# SmartSoilSensor.net
KiCad netlist of a schematic drawn in EAGLE
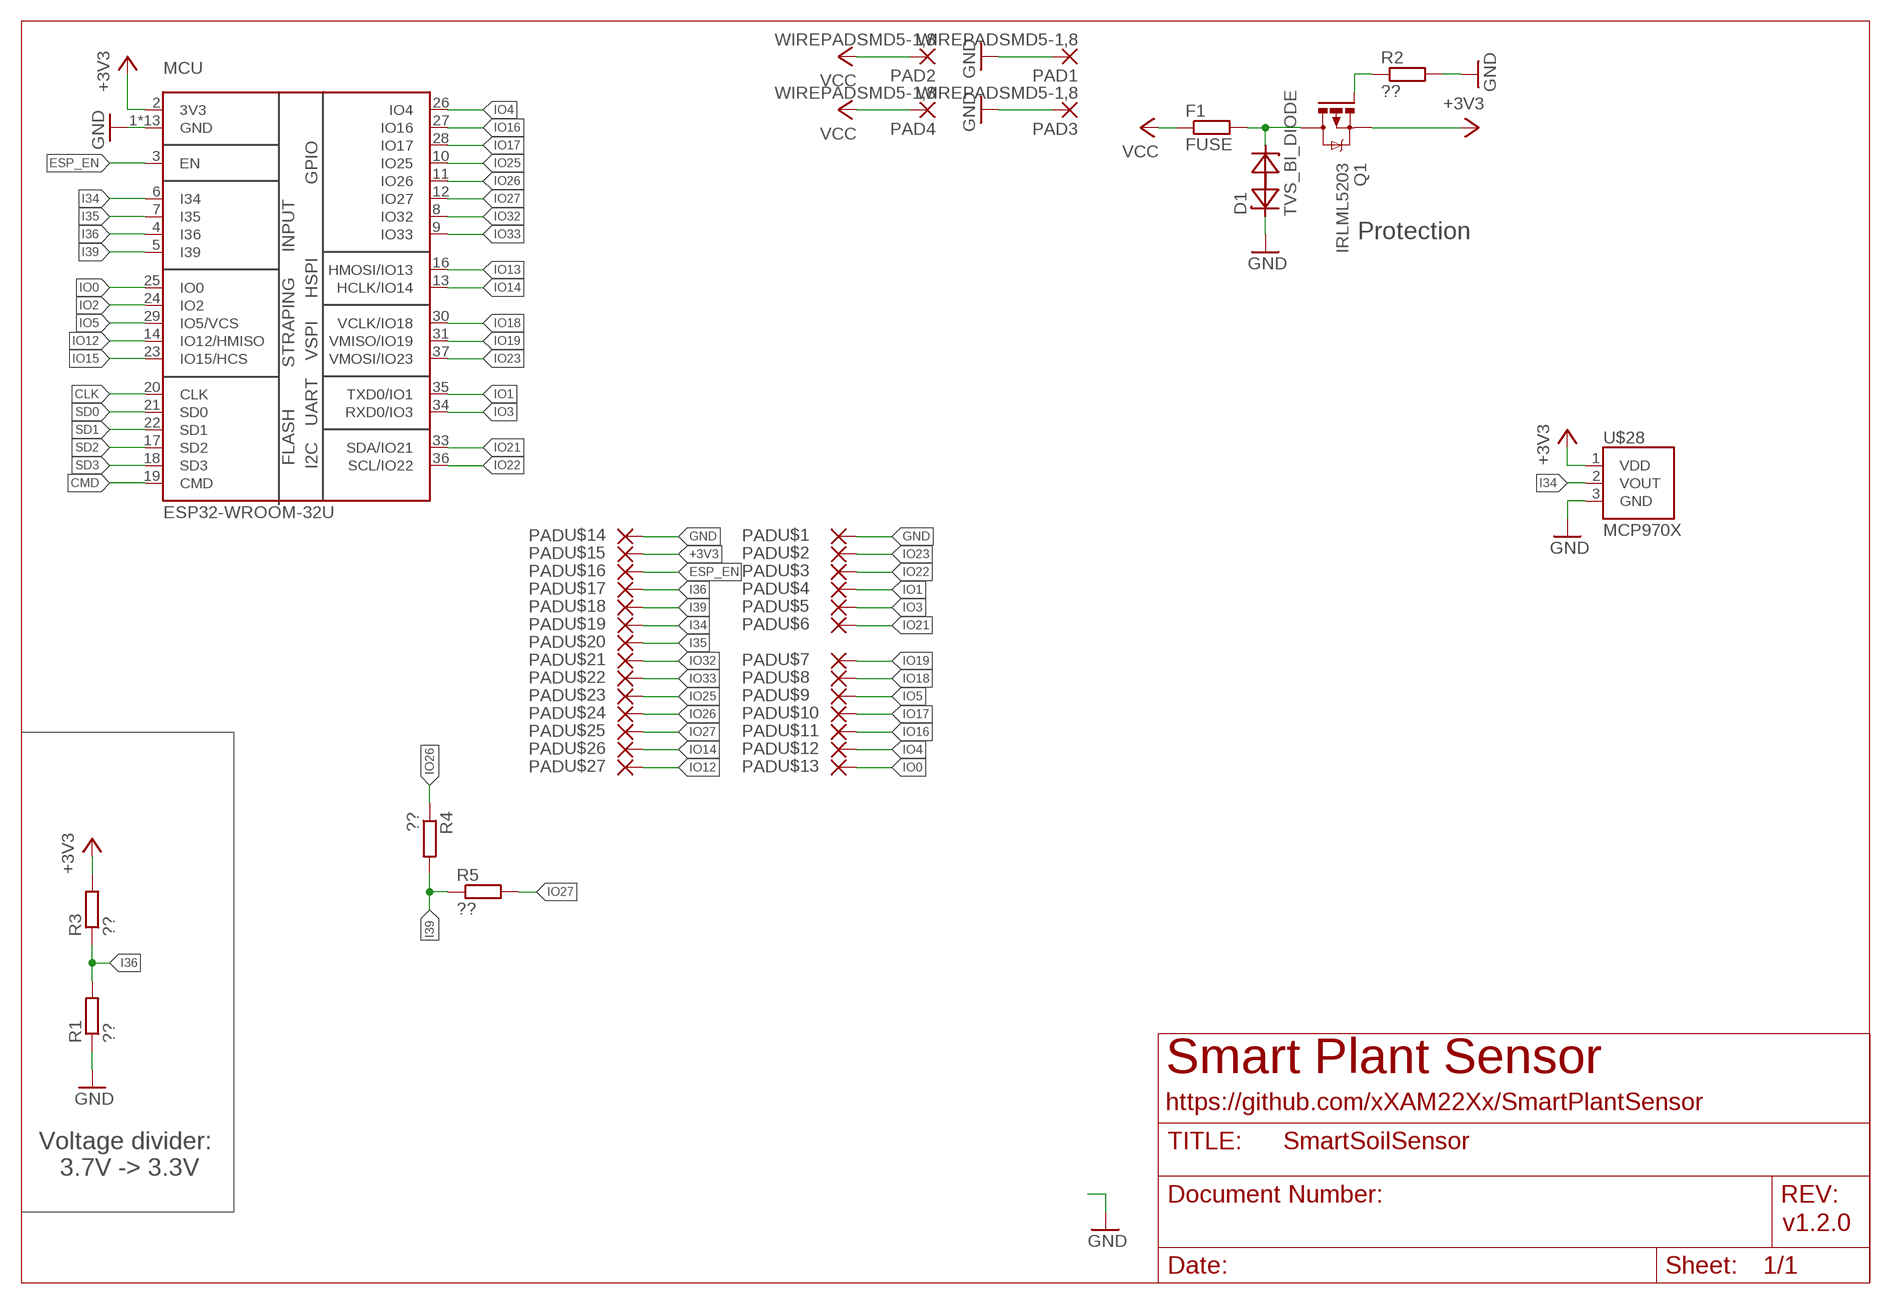
[diagram p0: schematic, sheet 1]

(export (version "E")
  (design (tool "Eeschema 10.0.6"))
  (components
    (comp (ref "D1")
      (value "TVS_BI_DIODE")
      (footprint "eagle-import:R0603")
      (libsource (lib "eagle-import") (part "TVS_BI_DIODE"))
    )
    (comp (ref "F1")
      (value "FUSE")
      (footprint "eagle-import:R1206")
      (libsource (lib "eagle-import") (part "R-EU_R1206"))
    )
    (comp (ref "MCU")
      (value "ESP32-WROOM-32U")
      (footprint "eagle-import:ESP32-WROOM-32U")
      (libsource (lib "eagle-import") (part "ESP32-WROOM-32U"))
    )
    (comp (ref "PAD1")
      (value "WIREPADSMD5-1,8")
      (footprint "eagle-import:5-1,8")
      (libsource (lib "eagle-import") (part "WIREPADSMD5-1,8"))
    )
    (comp (ref "PAD2")
      (value "WIREPADSMD5-1,8")
      (footprint "eagle-import:5-1,8")
      (libsource (lib "eagle-import") (part "WIREPADSMD5-1,8"))
    )
    (comp (ref "PAD3")
      (value "WIREPADSMD5-1,8")
      (footprint "eagle-import:5-1,8")
      (libsource (lib "eagle-import") (part "WIREPADSMD5-1,8"))
    )
    (comp (ref "PAD4")
      (value "WIREPADSMD5-1,8")
      (footprint "eagle-import:5-1,8")
      (libsource (lib "eagle-import") (part "WIREPADSMD5-1,8"))
    )
    (comp (ref "Q1")
      (value "IRLML5203")
      (footprint "eagle-import:MICRO3")
      (libsource (lib "eagle-import") (part "IRLML5203"))
    )
    (comp (ref "R1")
      (value "??")
      (footprint "eagle-import:R0603")
      (libsource (lib "eagle-import") (part "R-EU_R0603"))
    )
    (comp (ref "R2")
      (value "??")
      (footprint "eagle-import:R0603")
      (libsource (lib "eagle-import") (part "R-EU_R0603"))
    )
    (comp (ref "R3")
      (value "??")
      (footprint "eagle-import:R0603")
      (libsource (lib "eagle-import") (part "R-EU_R0603"))
    )
    (comp (ref "R4")
      (value "??")
      (footprint "eagle-import:R0603")
      (libsource (lib "eagle-import") (part "R-EU_R0603"))
    )
    (comp (ref "R5")
      (value "??")
      (footprint "eagle-import:R0603")
      (libsource (lib "eagle-import") (part "R-EU_R0603"))
    )
    (comp (ref "U$1")
      (value "PAD")
      (footprint "eagle-import:PAD")
      (libsource (lib "eagle-import") (part "PAD"))
    )
    (comp (ref "U$2")
      (value "PAD")
      (footprint "eagle-import:PAD")
      (libsource (lib "eagle-import") (part "PAD"))
    )
    (comp (ref "U$3")
      (value "PAD")
      (footprint "eagle-import:PAD")
      (libsource (lib "eagle-import") (part "PAD"))
    )
    (comp (ref "U$4")
      (value "PAD")
      (footprint "eagle-import:PAD")
      (libsource (lib "eagle-import") (part "PAD"))
    )
    (comp (ref "U$5")
      (value "PAD")
      (footprint "eagle-import:PAD")
      (libsource (lib "eagle-import") (part "PAD"))
    )
    (comp (ref "U$6")
      (value "PAD")
      (footprint "eagle-import:PAD")
      (libsource (lib "eagle-import") (part "PAD"))
    )
    (comp (ref "U$7")
      (value "PAD")
      (footprint "eagle-import:PAD")
      (libsource (lib "eagle-import") (part "PAD"))
    )
    (comp (ref "U$8")
      (value "PAD")
      (footprint "eagle-import:PAD")
      (libsource (lib "eagle-import") (part "PAD"))
    )
    (comp (ref "U$9")
      (value "PAD")
      (footprint "eagle-import:PAD")
      (libsource (lib "eagle-import") (part "PAD"))
    )
    (comp (ref "U$10")
      (value "PAD")
      (footprint "eagle-import:PAD")
      (libsource (lib "eagle-import") (part "PAD"))
    )
    (comp (ref "U$11")
      (value "PAD")
      (footprint "eagle-import:PAD")
      (libsource (lib "eagle-import") (part "PAD"))
    )
    (comp (ref "U$12")
      (value "PAD")
      (footprint "eagle-import:PAD")
      (libsource (lib "eagle-import") (part "PAD"))
    )
    (comp (ref "U$13")
      (value "PAD")
      (footprint "eagle-import:PAD")
      (libsource (lib "eagle-import") (part "PAD"))
    )
    (comp (ref "U$14")
      (value "PAD")
      (footprint "eagle-import:PAD")
      (libsource (lib "eagle-import") (part "PAD"))
    )
    (comp (ref "U$15")
      (value "PAD")
      (footprint "eagle-import:PAD")
      (libsource (lib "eagle-import") (part "PAD"))
    )
    (comp (ref "U$16")
      (value "PAD")
      (footprint "eagle-import:PAD")
      (libsource (lib "eagle-import") (part "PAD"))
    )
    (comp (ref "U$17")
      (value "PAD")
      (footprint "eagle-import:PAD")
      (libsource (lib "eagle-import") (part "PAD"))
    )
    (comp (ref "U$18")
      (value "PAD")
      (footprint "eagle-import:PAD")
      (libsource (lib "eagle-import") (part "PAD"))
    )
    (comp (ref "U$19")
      (value "PAD")
      (footprint "eagle-import:PAD")
      (libsource (lib "eagle-import") (part "PAD"))
    )
    (comp (ref "U$20")
      (value "PAD")
      (footprint "eagle-import:PAD")
      (libsource (lib "eagle-import") (part "PAD"))
    )
    (comp (ref "U$21")
      (value "PAD")
      (footprint "eagle-import:PAD")
      (libsource (lib "eagle-import") (part "PAD"))
    )
    (comp (ref "U$22")
      (value "PAD")
      (footprint "eagle-import:PAD")
      (libsource (lib "eagle-import") (part "PAD"))
    )
    (comp (ref "U$23")
      (value "PAD")
      (footprint "eagle-import:PAD")
      (libsource (lib "eagle-import") (part "PAD"))
    )
    (comp (ref "U$24")
      (value "PAD")
      (footprint "eagle-import:PAD")
      (libsource (lib "eagle-import") (part "PAD"))
    )
    (comp (ref "U$25")
      (value "PAD")
      (footprint "eagle-import:PAD")
      (libsource (lib "eagle-import") (part "PAD"))
    )
    (comp (ref "U$26")
      (value "PAD")
      (footprint "eagle-import:PAD")
      (libsource (lib "eagle-import") (part "PAD"))
    )
    (comp (ref "U$27")
      (value "PAD")
      (footprint "eagle-import:PAD")
      (libsource (lib "eagle-import") (part "PAD"))
    )
    (comp (ref "U$28")
      (value "MCP970X")
      (footprint "eagle-import:MCP970X")
      (libsource (lib "eagle-import") (part "MCP970X"))
    )
  )
  (nets
    (net (code "1") (name "+3V3") (class "Default")
      (node (ref "MCU") (pin "2") (pinfunction "3V3_2") (pintype "power_in"))
      (node (ref "Q1") (pin "2") (pinfunction "S_2") (pintype "passive"))
      (node (ref "R3") (pin "2") (pinfunction "2_2") (pintype "passive"))
      (node (ref "U$15") (pin "P$1") (pinfunction "P_P$1") (pintype "passive"))
      (node (ref "U$28") (pin "1") (pinfunction "VDD_1") (pintype "bidirectional"))
    )
    (net (code "2") (name "CLK") (class "Default")
      (node (ref "MCU") (pin "20") (pinfunction "CLK_20") (pintype "bidirectional"))
    )
    (net (code "3") (name "CMD") (class "Default")
      (node (ref "MCU") (pin "19") (pinfunction "CMD_19") (pintype "bidirectional"))
    )
    (net (code "4") (name "ESP_EN") (class "Default")
      (node (ref "MCU") (pin "3") (pinfunction "EN_3") (pintype "input"))
      (node (ref "U$16") (pin "P$1") (pinfunction "P_P$1") (pintype "passive"))
    )
    (net (code "5") (name "GND") (class "Default")
      (node (ref "D1") (pin "1") (pinfunction "A_1") (pintype "passive"))
      (node (ref "MCU") (pin "1") (pinfunction "GND_1") (pintype "power_in"))
      (node (ref "MCU") (pin "15") (pinfunction "GND_15") (pintype "power_in"))
      (node (ref "MCU") (pin "38") (pinfunction "GND_38") (pintype "power_in"))
      (node (ref "MCU") (pin "39") (pinfunction "GND_39") (pintype "power_in"))
      (node (ref "MCU") (pin "P$1") (pinfunction "GND_P$1") (pintype "power_in"))
      (node (ref "MCU") (pin "P$2") (pinfunction "GND_P$2") (pintype "power_in"))
      (node (ref "MCU") (pin "P$3") (pinfunction "GND_P$3") (pintype "power_in"))
      (node (ref "MCU") (pin "P$4") (pinfunction "GND_P$4") (pintype "power_in"))
      (node (ref "MCU") (pin "P$5") (pinfunction "GND_P$5") (pintype "power_in"))
      (node (ref "MCU") (pin "P$6") (pinfunction "GND_P$6") (pintype "power_in"))
      (node (ref "MCU") (pin "P$7") (pinfunction "GND_P$7") (pintype "power_in"))
      (node (ref "MCU") (pin "P$8") (pinfunction "GND_P$8") (pintype "power_in"))
      (node (ref "MCU") (pin "P$9") (pinfunction "GND_P$9") (pintype "power_in"))
      (node (ref "PAD1") (pin "1") (pinfunction "P_1") (pintype "passive"))
      (node (ref "PAD3") (pin "1") (pinfunction "P_1") (pintype "passive"))
      (node (ref "R1") (pin "1") (pinfunction "1_1") (pintype "passive"))
      (node (ref "R2") (pin "2") (pinfunction "2_2") (pintype "passive"))
      (node (ref "U$1") (pin "P$1") (pinfunction "P_P$1") (pintype "passive"))
      (node (ref "U$14") (pin "P$1") (pinfunction "P_P$1") (pintype "passive"))
      (node (ref "U$28") (pin "3") (pinfunction "GND_3") (pintype "bidirectional"))
    )
    (net (code "6") (name "I34") (class "Default")
      (node (ref "MCU") (pin "6") (pinfunction "I34_6") (pintype "input"))
      (node (ref "U$19") (pin "P$1") (pinfunction "P_P$1") (pintype "passive"))
      (node (ref "U$28") (pin "2") (pinfunction "VOUT_2") (pintype "bidirectional"))
    )
    (net (code "7") (name "I35") (class "Default")
      (node (ref "MCU") (pin "7") (pinfunction "I35_7") (pintype "input"))
      (node (ref "U$20") (pin "P$1") (pinfunction "P_P$1") (pintype "passive"))
    )
    (net (code "8") (name "I36") (class "Default")
      (node (ref "MCU") (pin "4") (pinfunction "I36_4") (pintype "input"))
      (node (ref "R1") (pin "2") (pinfunction "2_2") (pintype "passive"))
      (node (ref "R3") (pin "1") (pinfunction "1_1") (pintype "passive"))
      (node (ref "U$17") (pin "P$1") (pinfunction "P_P$1") (pintype "passive"))
    )
    (net (code "9") (name "I39") (class "Default")
      (node (ref "MCU") (pin "5") (pinfunction "I39_5") (pintype "input"))
      (node (ref "R4") (pin "2") (pinfunction "2_2") (pintype "passive"))
      (node (ref "R5") (pin "1") (pinfunction "1_1") (pintype "passive"))
      (node (ref "U$18") (pin "P$1") (pinfunction "P_P$1") (pintype "passive"))
    )
    (net (code "10") (name "IO0") (class "Default")
      (node (ref "MCU") (pin "25") (pinfunction "IO0_25") (pintype "bidirectional"))
      (node (ref "U$13") (pin "P$1") (pinfunction "P_P$1") (pintype "passive"))
    )
    (net (code "11") (name "IO1") (class "Default")
      (node (ref "MCU") (pin "35") (pinfunction "TXD0/IO1_35") (pintype "bidirectional"))
      (node (ref "U$4") (pin "P$1") (pinfunction "P_P$1") (pintype "passive"))
    )
    (net (code "12") (name "IO2") (class "Default")
      (node (ref "MCU") (pin "24") (pinfunction "IO2_24") (pintype "bidirectional"))
    )
    (net (code "13") (name "IO3") (class "Default")
      (node (ref "MCU") (pin "34") (pinfunction "RXD0/IO3_34") (pintype "bidirectional"))
      (node (ref "U$5") (pin "P$1") (pinfunction "P_P$1") (pintype "passive"))
    )
    (net (code "14") (name "IO4") (class "Default")
      (node (ref "MCU") (pin "26") (pinfunction "IO4_26") (pintype "bidirectional"))
      (node (ref "U$12") (pin "P$1") (pinfunction "P_P$1") (pintype "passive"))
    )
    (net (code "15") (name "IO5") (class "Default")
      (node (ref "MCU") (pin "29") (pinfunction "IO5/VCS_29") (pintype "bidirectional"))
      (node (ref "U$9") (pin "P$1") (pinfunction "P_P$1") (pintype "passive"))
    )
    (net (code "16") (name "IO12") (class "Default")
      (node (ref "MCU") (pin "14") (pinfunction "IO12/HMISO_14") (pintype "bidirectional"))
      (node (ref "U$27") (pin "P$1") (pinfunction "P_P$1") (pintype "passive"))
    )
    (net (code "17") (name "IO13") (class "Default")
      (node (ref "MCU") (pin "16") (pinfunction "HMOSI/IO13_16") (pintype "bidirectional"))
    )
    (net (code "18") (name "IO14") (class "Default")
      (node (ref "MCU") (pin "13") (pinfunction "HCLK/IO14_13") (pintype "bidirectional"))
      (node (ref "U$26") (pin "P$1") (pinfunction "P_P$1") (pintype "passive"))
    )
    (net (code "19") (name "IO15") (class "Default")
      (node (ref "MCU") (pin "23") (pinfunction "IO15/HCS_23") (pintype "bidirectional"))
    )
    (net (code "20") (name "IO16") (class "Default")
      (node (ref "MCU") (pin "27") (pinfunction "IO16_27") (pintype "bidirectional"))
      (node (ref "U$11") (pin "P$1") (pinfunction "P_P$1") (pintype "passive"))
    )
    (net (code "21") (name "IO17") (class "Default")
      (node (ref "MCU") (pin "28") (pinfunction "IO17_28") (pintype "bidirectional"))
      (node (ref "U$10") (pin "P$1") (pinfunction "P_P$1") (pintype "passive"))
    )
    (net (code "22") (name "IO18") (class "Default")
      (node (ref "MCU") (pin "30") (pinfunction "VCLK/IO18_30") (pintype "bidirectional"))
      (node (ref "U$8") (pin "P$1") (pinfunction "P_P$1") (pintype "passive"))
    )
    (net (code "23") (name "IO19") (class "Default")
      (node (ref "MCU") (pin "31") (pinfunction "VMISO/IO19_31") (pintype "bidirectional"))
      (node (ref "U$7") (pin "P$1") (pinfunction "P_P$1") (pintype "passive"))
    )
    (net (code "24") (name "IO21") (class "Default")
      (node (ref "MCU") (pin "33") (pinfunction "SDA/IO21_33") (pintype "bidirectional"))
      (node (ref "U$6") (pin "P$1") (pinfunction "P_P$1") (pintype "passive"))
    )
    (net (code "25") (name "IO22") (class "Default")
      (node (ref "MCU") (pin "36") (pinfunction "SCL/IO22_36") (pintype "bidirectional"))
      (node (ref "U$3") (pin "P$1") (pinfunction "P_P$1") (pintype "passive"))
    )
    (net (code "26") (name "IO23") (class "Default")
      (node (ref "MCU") (pin "37") (pinfunction "VMOSI/IO23_37") (pintype "bidirectional"))
      (node (ref "U$2") (pin "P$1") (pinfunction "P_P$1") (pintype "passive"))
    )
    (net (code "27") (name "IO25") (class "Default")
      (node (ref "MCU") (pin "10") (pinfunction "IO25_10") (pintype "bidirectional"))
      (node (ref "U$23") (pin "P$1") (pinfunction "P_P$1") (pintype "passive"))
    )
    (net (code "28") (name "IO26") (class "Default")
      (node (ref "MCU") (pin "11") (pinfunction "IO26_11") (pintype "bidirectional"))
      (node (ref "R4") (pin "1") (pinfunction "1_1") (pintype "passive"))
      (node (ref "U$24") (pin "P$1") (pinfunction "P_P$1") (pintype "passive"))
    )
    (net (code "29") (name "IO27") (class "Default")
      (node (ref "MCU") (pin "12") (pinfunction "IO27_12") (pintype "bidirectional"))
      (node (ref "R5") (pin "2") (pinfunction "2_2") (pintype "passive"))
      (node (ref "U$25") (pin "P$1") (pinfunction "P_P$1") (pintype "passive"))
    )
    (net (code "30") (name "IO32") (class "Default")
      (node (ref "MCU") (pin "8") (pinfunction "IO32_8") (pintype "bidirectional"))
      (node (ref "U$21") (pin "P$1") (pinfunction "P_P$1") (pintype "passive"))
    )
    (net (code "31") (name "IO33") (class "Default")
      (node (ref "MCU") (pin "9") (pinfunction "IO33_9") (pintype "bidirectional"))
      (node (ref "U$22") (pin "P$1") (pinfunction "P_P$1") (pintype "passive"))
    )
    (net (code "32") (name "Net-(D1-C)") (class "Default")
      (node (ref "D1") (pin "2") (pinfunction "C_2") (pintype "passive"))
      (node (ref "F1") (pin "2") (pinfunction "2_2") (pintype "passive"))
      (node (ref "Q1") (pin "3") (pinfunction "D_3") (pintype "passive"))
    )
    (net (code "33") (name "Net-(Q1-G)") (class "Default")
      (node (ref "Q1") (pin "1") (pinfunction "G_1") (pintype "passive"))
      (node (ref "R2") (pin "1") (pinfunction "1_1") (pintype "passive"))
    )
    (net (code "34") (name "SD0") (class "Default")
      (node (ref "MCU") (pin "21") (pinfunction "SD0_21") (pintype "bidirectional"))
    )
    (net (code "35") (name "SD1") (class "Default")
      (node (ref "MCU") (pin "22") (pinfunction "SD1_22") (pintype "bidirectional"))
    )
    (net (code "36") (name "SD2") (class "Default")
      (node (ref "MCU") (pin "17") (pinfunction "SD2_17") (pintype "bidirectional"))
    )
    (net (code "37") (name "SD3") (class "Default")
      (node (ref "MCU") (pin "18") (pinfunction "SD3_18") (pintype "bidirectional"))
    )
    (net (code "38") (name "VCC") (class "Default")
      (node (ref "F1") (pin "1") (pinfunction "1_1") (pintype "passive"))
      (node (ref "PAD2") (pin "1") (pinfunction "P_1") (pintype "passive"))
      (node (ref "PAD4") (pin "1") (pinfunction "P_1") (pintype "passive"))
    )
  )
)
